# Wash_Hand_v1_1.net
KiCad netlist of a schematic drawn in EAGLE
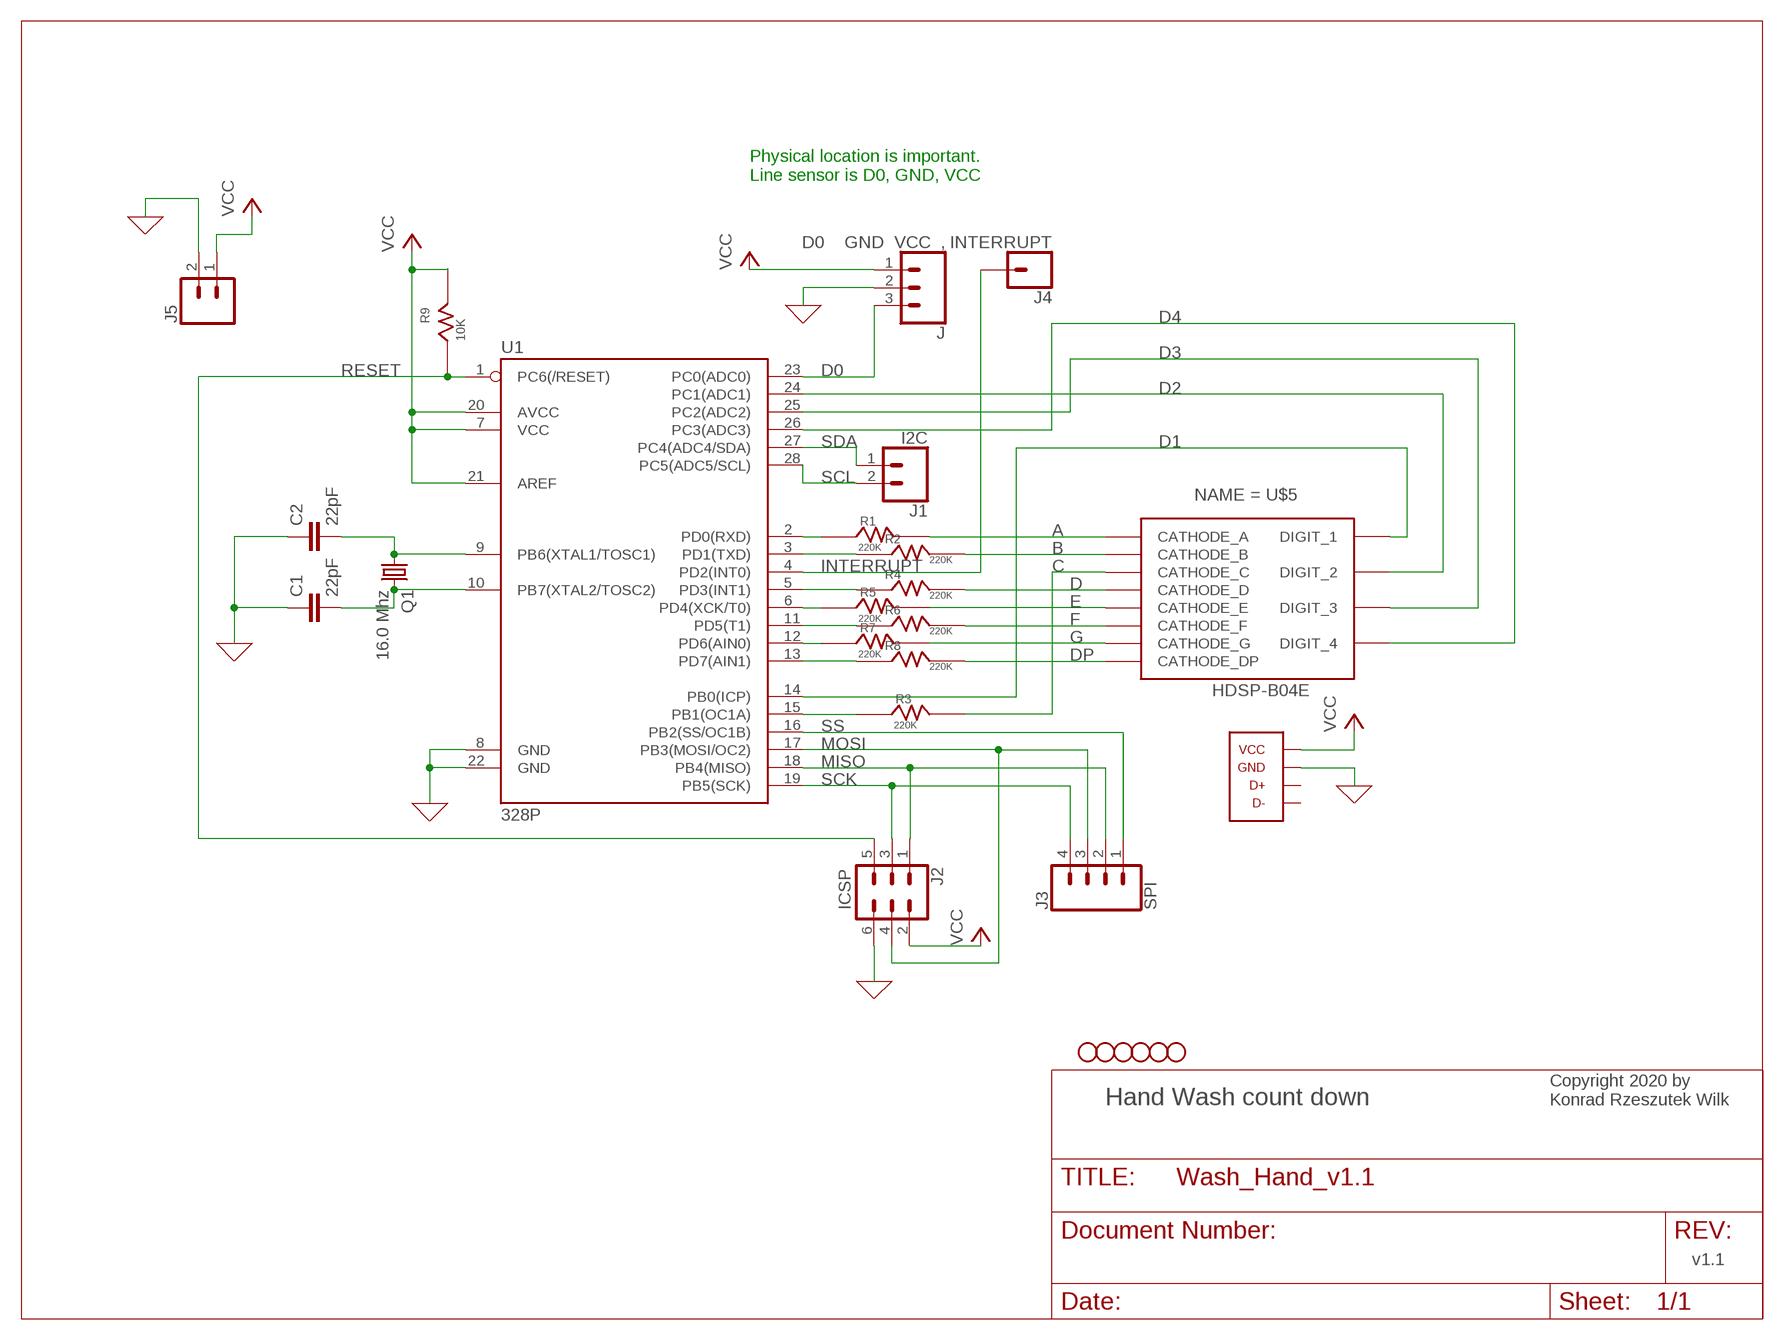
[diagram p0: schematic, sheet 1]

(export (version "E")
  (design (tool "Eeschema 10.0.6"))
  (components
    (comp (ref "C1")
      (value "22pF")
      (footprint "eagle-import:CAP-PTH-2.54")
      (libsource (lib "eagle-import") (part "22PF-PTH-2.54MM-200V-5%"))
    )
    (comp (ref "C2")
      (value "22pF")
      (footprint "eagle-import:CAP-PTH-2.54")
      (libsource (lib "eagle-import") (part "22PF-PTH-2.54MM-200V-5%"))
    )
    (comp (ref "H1")
      (value "STAND-OFF")
      (footprint "eagle-import:STAND-OFF")
      (libsource (lib "eagle-import") (part "STAND-OFF"))
    )
    (comp (ref "H2")
      (value "STAND-OFF")
      (footprint "eagle-import:STAND-OFF")
      (libsource (lib "eagle-import") (part "STAND-OFF"))
    )
    (comp (ref "H3")
      (value "STAND-OFF")
      (footprint "eagle-import:STAND-OFF")
      (libsource (lib "eagle-import") (part "STAND-OFF"))
    )
    (comp (ref "H4")
      (value "STAND-OFF")
      (footprint "eagle-import:STAND-OFF")
      (libsource (lib "eagle-import") (part "STAND-OFF"))
    )
    (comp (ref "H5")
      (value "STAND-OFF")
      (footprint "eagle-import:STAND-OFF")
      (libsource (lib "eagle-import") (part "STAND-OFF"))
    )
    (comp (ref "H6")
      (value "STAND-OFF")
      (footprint "eagle-import:STAND-OFF")
      (libsource (lib "eagle-import") (part "STAND-OFF"))
    )
    (comp (ref "J")
      (value "D0 GND VCC ,")
      (footprint "eagle-import:1X03")
      (libsource (lib "eagle-import") (part "CONN_03"))
    )
    (comp (ref "J1")
      (value "I2C")
      (footprint "eagle-import:1X02")
      (libsource (lib "eagle-import") (part "CONN_02"))
    )
    (comp (ref "J2")
      (value "ICSP")
      (footprint "eagle-import:2X3")
      (libsource (lib "eagle-import") (part "CONN_03X2FEMALE"))
    )
    (comp (ref "J3")
      (value "SPI")
      (footprint "eagle-import:1X04")
      (libsource (lib "eagle-import") (part "CONN_04"))
    )
    (comp (ref "J4")
      (value "INTERRUPT")
      (footprint "eagle-import:1X01")
      (libsource (lib "eagle-import") (part "CONN_01"))
    )
    (comp (ref "J5")
      (value "CONN_02")
      (footprint "eagle-import:1X02")
      (libsource (lib "eagle-import") (part "CONN_02"))
    )
    (comp (ref "Q1")
      (value "16.0 Mhz")
      (footprint "eagle-import:HC49_S")
      (libsource (lib "eagle-import") (part "CRYSTALHC49S"))
    )
    (comp (ref "R1")
      (value "220K")
      (footprint "eagle-import:RESISTOR")
      (libsource (lib "eagle-import") (part "RESISTOR"))
    )
    (comp (ref "R2")
      (value "220K")
      (footprint "eagle-import:RESISTOR")
      (libsource (lib "eagle-import") (part "RESISTOR"))
    )
    (comp (ref "R3")
      (value "220K")
      (footprint "eagle-import:RESISTOR")
      (libsource (lib "eagle-import") (part "RESISTOR"))
    )
    (comp (ref "R4")
      (value "220K")
      (footprint "eagle-import:RESISTOR")
      (libsource (lib "eagle-import") (part "RESISTOR"))
    )
    (comp (ref "R5")
      (value "220K")
      (footprint "eagle-import:RESISTOR")
      (libsource (lib "eagle-import") (part "RESISTOR"))
    )
    (comp (ref "R6")
      (value "220K")
      (footprint "eagle-import:RESISTOR")
      (libsource (lib "eagle-import") (part "RESISTOR"))
    )
    (comp (ref "R7")
      (value "220K")
      (footprint "eagle-import:RESISTOR")
      (libsource (lib "eagle-import") (part "RESISTOR"))
    )
    (comp (ref "R8")
      (value "220K")
      (footprint "eagle-import:RESISTOR")
      (libsource (lib "eagle-import") (part "RESISTOR"))
    )
    (comp (ref "R9")
      (value "10K")
      (footprint "eagle-import:RESISTOR")
      (libsource (lib "eagle-import") (part "RESISTOR"))
    )
    (comp (ref "U$4")
      (value "USB_MICROB_10118194_AMPHENOL")
      (footprint "eagle-import:USB_MICROB_10118194_AMPHENOL")
      (libsource (lib "eagle-import") (part "USB_MICROB_10118194_AMPHENOL"))
    )
    (comp (ref "U$5")
      (value "HDSP-B04E")
      (footprint "eagle-import:HDSP-B0XE")
      (libsource (lib "eagle-import") (part "HDSP-B04E"))
    )
    (comp (ref "U1")
      (value "328P")
      (footprint "eagle-import:DIP28")
      (libsource (lib "eagle-import") (part "ATMEGA328P_PDIP"))
    )
  )
  (nets
    (net (code "1") (name "/A") (class "Default")
      (node (ref "R1") (pin "R_2") (pinfunction "R_2_R_2") (pintype "bidirectional"))
      (node (ref "U$5") (pin "PIN$11") (pinfunction "CATHODE_A_PIN$11") (pintype "input"))
    )
    (net (code "2") (name "/B") (class "Default")
      (node (ref "R2") (pin "R_2") (pinfunction "R_2_R_2") (pintype "bidirectional"))
      (node (ref "U$5") (pin "PIN$7") (pinfunction "CATHODE_B_PIN$7") (pintype "input"))
    )
    (net (code "3") (name "/C") (class "Default")
      (node (ref "R3") (pin "R_2") (pinfunction "R_2_R_2") (pintype "bidirectional"))
      (node (ref "U$5") (pin "PIN$4") (pinfunction "CATHODE_C_PIN$4") (pintype "input"))
    )
    (net (code "4") (name "/D") (class "Default")
      (node (ref "R4") (pin "R_2") (pinfunction "R_2_R_2") (pintype "bidirectional"))
      (node (ref "U$5") (pin "PIN$2") (pinfunction "CATHODE_D_PIN$2") (pintype "input"))
    )
    (net (code "5") (name "/D0") (class "Default")
      (node (ref "J") (pin "3") (pinfunction "3_3") (pintype "passive"))
      (node (ref "U1") (pin "23") (pinfunction "PC0(ADC0)_23") (pintype "bidirectional"))
    )
    (net (code "6") (name "/D1") (class "Default")
      (node (ref "U$5") (pin "PIN12") (pinfunction "DIGIT_1_PIN12") (pintype "input"))
      (node (ref "U1") (pin "14") (pinfunction "PB0(ICP)_14") (pintype "bidirectional"))
    )
    (net (code "7") (name "/D2") (class "Default")
      (node (ref "U$5") (pin "PIN$9") (pinfunction "DIGIT_2_PIN$9") (pintype "input"))
      (node (ref "U1") (pin "24") (pinfunction "PC1(ADC1)_24") (pintype "bidirectional"))
    )
    (net (code "8") (name "/D3") (class "Default")
      (node (ref "U$5") (pin "PIN$8") (pinfunction "DIGIT_3_PIN$8") (pintype "input"))
      (node (ref "U1") (pin "25") (pinfunction "PC2(ADC2)_25") (pintype "bidirectional"))
    )
    (net (code "9") (name "/D4") (class "Default")
      (node (ref "U$5") (pin "PIN$6") (pinfunction "DIGIT_4_PIN$6") (pintype "input"))
      (node (ref "U1") (pin "26") (pinfunction "PC3(ADC3)_26") (pintype "bidirectional"))
    )
    (net (code "10") (name "/DP") (class "Default")
      (node (ref "R8") (pin "R_2") (pinfunction "R_2_R_2") (pintype "bidirectional"))
      (node (ref "U$5") (pin "PIN$3") (pinfunction "CATHODE_DP_PIN$3") (pintype "input"))
    )
    (net (code "11") (name "/E") (class "Default")
      (node (ref "R5") (pin "R_2") (pinfunction "R_2_R_2") (pintype "bidirectional"))
      (node (ref "U$5") (pin "PIN$1") (pinfunction "CATHODE_E_PIN$1") (pintype "input"))
    )
    (net (code "12") (name "/F") (class "Default")
      (node (ref "R6") (pin "R_2") (pinfunction "R_2_R_2") (pintype "bidirectional"))
      (node (ref "U$5") (pin "PIN$10") (pinfunction "CATHODE_F_PIN$10") (pintype "input"))
    )
    (net (code "13") (name "/G") (class "Default")
      (node (ref "R7") (pin "R_2") (pinfunction "R_2_R_2") (pintype "bidirectional"))
      (node (ref "U$5") (pin "PIN$5") (pinfunction "CATHODE_G_PIN$5") (pintype "input"))
    )
    (net (code "14") (name "/INTERRUPT") (class "Default")
      (node (ref "J4") (pin "1") (pinfunction "1_1") (pintype "passive"))
      (node (ref "U1") (pin "4") (pinfunction "PD2(INT0)_4") (pintype "bidirectional"))
    )
    (net (code "15") (name "/MISO") (class "Default")
      (node (ref "J2") (pin "1") (pinfunction "1_1") (pintype "bidirectional"))
      (node (ref "J3") (pin "2") (pinfunction "2_2") (pintype "passive"))
      (node (ref "U1") (pin "18") (pinfunction "PB4(MISO)_18") (pintype "bidirectional"))
    )
    (net (code "16") (name "/MOSI") (class "Default")
      (node (ref "J2") (pin "4") (pinfunction "4_4") (pintype "bidirectional"))
      (node (ref "J3") (pin "3") (pinfunction "3_3") (pintype "passive"))
      (node (ref "U1") (pin "17") (pinfunction "PB3(MOSI/OC2)_17") (pintype "bidirectional"))
    )
    (net (code "17") (name "/RESET") (class "Default")
      (node (ref "J2") (pin "5") (pinfunction "5_5") (pintype "bidirectional"))
      (node (ref "R9") (pin "R_1") (pinfunction "R_1_R_1") (pintype "bidirectional"))
      (node (ref "U1") (pin "1") (pinfunction "PC6(/RESET)_1") (pintype "bidirectional"))
    )
    (net (code "18") (name "/SCK") (class "Default")
      (node (ref "J2") (pin "3") (pinfunction "3_3") (pintype "bidirectional"))
      (node (ref "J3") (pin "4") (pinfunction "4_4") (pintype "passive"))
      (node (ref "U1") (pin "19") (pinfunction "PB5(SCK)_19") (pintype "bidirectional"))
    )
    (net (code "19") (name "/SCL") (class "Default")
      (node (ref "J1") (pin "2") (pinfunction "2_2") (pintype "passive"))
      (node (ref "U1") (pin "28") (pinfunction "PC5(ADC5/SCL)_28") (pintype "bidirectional"))
    )
    (net (code "20") (name "/SDA") (class "Default")
      (node (ref "J1") (pin "1") (pinfunction "1_1") (pintype "passive"))
      (node (ref "U1") (pin "27") (pinfunction "PC4(ADC4/SDA)_27") (pintype "bidirectional"))
    )
    (net (code "21") (name "/SS") (class "Default")
      (node (ref "J3") (pin "1") (pinfunction "1_1") (pintype "passive"))
      (node (ref "U1") (pin "16") (pinfunction "PB2(SS/OC1B)_16") (pintype "bidirectional"))
    )
    (net (code "22") (name "GND") (class "Default")
      (node (ref "C1") (pin "1") (pinfunction "1_1") (pintype "passive"))
      (node (ref "C2") (pin "1") (pinfunction "1_1") (pintype "passive"))
      (node (ref "J") (pin "2") (pinfunction "2_2") (pintype "passive"))
      (node (ref "J2") (pin "6") (pinfunction "6_6") (pintype "bidirectional"))
      (node (ref "J5") (pin "2") (pinfunction "2_2") (pintype "passive"))
      (node (ref "U$4") (pin "5") (pinfunction "GND_5") (pintype "bidirectional"))
      (node (ref "U1") (pin "22") (pinfunction "GND_22") (pintype "bidirectional"))
      (node (ref "U1") (pin "8") (pinfunction "GND_8") (pintype "bidirectional"))
    )
    (net (code "23") (name "Net-(U1-PB1(OC1A))") (class "Default")
      (node (ref "R3") (pin "R_1") (pinfunction "R_1_R_1") (pintype "bidirectional"))
      (node (ref "U1") (pin "15") (pinfunction "PB1(OC1A)_15") (pintype "bidirectional"))
    )
    (net (code "24") (name "Net-(U1-PB6(XTAL1{slash}TOSC1))") (class "Default")
      (node (ref "C2") (pin "2") (pinfunction "2_2") (pintype "passive"))
      (node (ref "Q1") (pin "1") (pinfunction "1_1") (pintype "passive"))
      (node (ref "U1") (pin "9") (pinfunction "PB6(XTAL1/TOSC1)_9") (pintype "bidirectional"))
    )
    (net (code "25") (name "Net-(U1-PB7(XTAL2{slash}TOSC2))") (class "Default")
      (node (ref "C1") (pin "2") (pinfunction "2_2") (pintype "passive"))
      (node (ref "Q1") (pin "2") (pinfunction "2_2") (pintype "passive"))
      (node (ref "U1") (pin "10") (pinfunction "PB7(XTAL2/TOSC2)_10") (pintype "bidirectional"))
    )
    (net (code "26") (name "Net-(U1-PD0(RXD))") (class "Default")
      (node (ref "R1") (pin "R_1") (pinfunction "R_1_R_1") (pintype "bidirectional"))
      (node (ref "U1") (pin "2") (pinfunction "PD0(RXD)_2") (pintype "bidirectional"))
    )
    (net (code "27") (name "Net-(U1-PD1(TXD))") (class "Default")
      (node (ref "R2") (pin "R_1") (pinfunction "R_1_R_1") (pintype "bidirectional"))
      (node (ref "U1") (pin "3") (pinfunction "PD1(TXD)_3") (pintype "bidirectional"))
    )
    (net (code "28") (name "Net-(U1-PD3(INT1))") (class "Default")
      (node (ref "R4") (pin "R_1") (pinfunction "R_1_R_1") (pintype "bidirectional"))
      (node (ref "U1") (pin "5") (pinfunction "PD3(INT1)_5") (pintype "bidirectional"))
    )
    (net (code "29") (name "Net-(U1-PD4(XCK{slash}T0))") (class "Default")
      (node (ref "R5") (pin "R_1") (pinfunction "R_1_R_1") (pintype "bidirectional"))
      (node (ref "U1") (pin "6") (pinfunction "PD4(XCK/T0)_6") (pintype "bidirectional"))
    )
    (net (code "30") (name "Net-(U1-PD5(T1))") (class "Default")
      (node (ref "R6") (pin "R_1") (pinfunction "R_1_R_1") (pintype "bidirectional"))
      (node (ref "U1") (pin "11") (pinfunction "PD5(T1)_11") (pintype "bidirectional"))
    )
    (net (code "31") (name "Net-(U1-PD6(AIN0))") (class "Default")
      (node (ref "R7") (pin "R_1") (pinfunction "R_1_R_1") (pintype "bidirectional"))
      (node (ref "U1") (pin "12") (pinfunction "PD6(AIN0)_12") (pintype "bidirectional"))
    )
    (net (code "32") (name "Net-(U1-PD7(AIN1))") (class "Default")
      (node (ref "R8") (pin "R_1") (pinfunction "R_1_R_1") (pintype "bidirectional"))
      (node (ref "U1") (pin "13") (pinfunction "PD7(AIN1)_13") (pintype "bidirectional"))
    )
    (net (code "33") (name "VCC") (class "Default")
      (node (ref "J") (pin "1") (pinfunction "1_1") (pintype "passive"))
      (node (ref "J2") (pin "2") (pinfunction "2_2") (pintype "bidirectional"))
      (node (ref "J5") (pin "1") (pinfunction "1_1") (pintype "passive"))
      (node (ref "R9") (pin "R_2") (pinfunction "R_2_R_2") (pintype "bidirectional"))
      (node (ref "U$4") (pin "1") (pinfunction "VCC_1") (pintype "bidirectional"))
      (node (ref "U1") (pin "20") (pinfunction "AVCC_20") (pintype "bidirectional"))
      (node (ref "U1") (pin "21") (pinfunction "AREF_21") (pintype "bidirectional"))
      (node (ref "U1") (pin "7") (pinfunction "VCC_7") (pintype "bidirectional"))
    )
    (net (code "34") (name "unconnected-(U$4-D+-Pad3)") (class "Default")
      (node (ref "U$4") (pin "3") (pinfunction "D+_3") (pintype "bidirectional"))
    )
    (net (code "35") (name "unconnected-(U$4-D--Pad2)") (class "Default")
      (node (ref "U$4") (pin "2") (pinfunction "D-_2") (pintype "bidirectional"))
    )
  )
)
